# Sheet1.net
KiCad netlist of a schematic drawn in Altium Designer
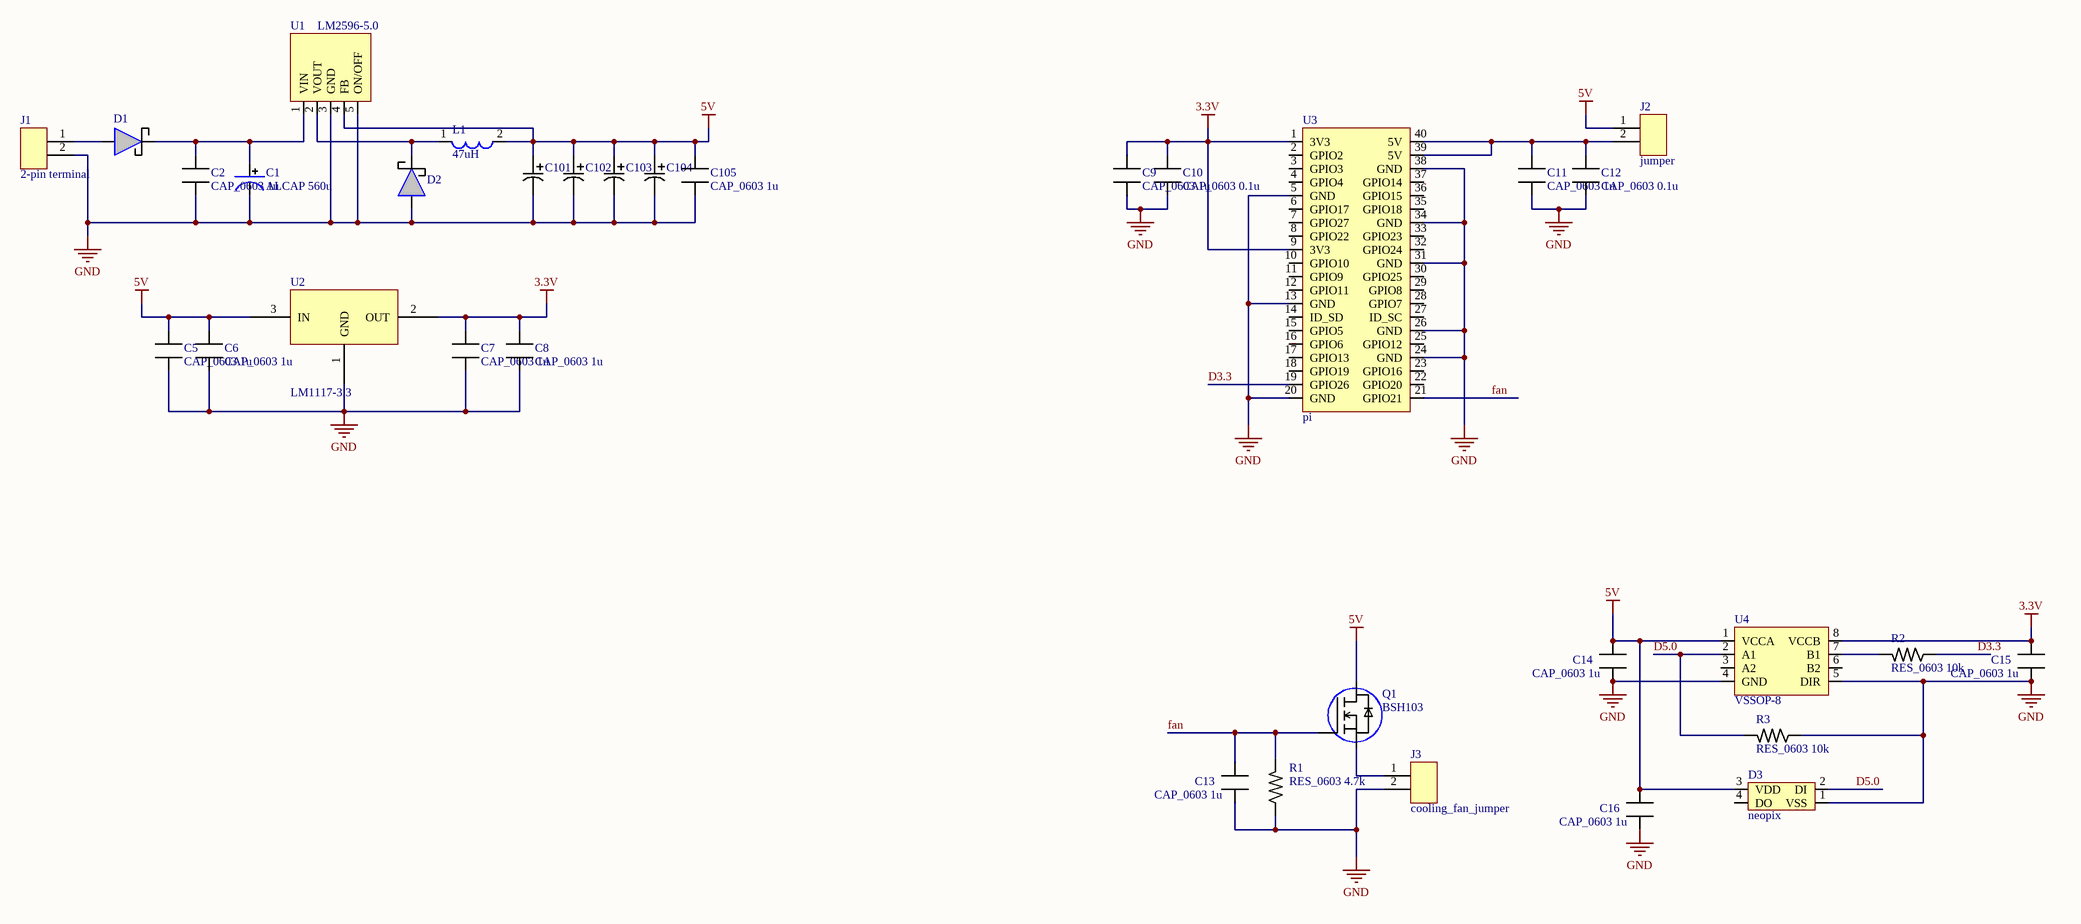
[diagram p0: Sheet1.SchDoc]

(export (version "E")
  (design (tool "Eeschema 10.0.6"))
  (components
    (comp (ref "C1")
      (value "ALCAP 560u")
      (footprint "alcap-560uF")
      (description "ALCAP")
      (libsource (lib "pi_powerhat") (part "ALCAP_47UF"))
    )
    (comp (ref "C2")
      (value "CAP_0603 1u")
      (footprint "CAP_0603")
      (description "CAP_0603")
      (libsource (lib "pi_powerhat") (part "CAP_0603"))
    )
    (comp (ref "C5")
      (value "CAP_0603 1u")
      (footprint "CAP_0603")
      (description "CAP_0603")
      (libsource (lib "pi_powerhat") (part "CAP_0603"))
    )
    (comp (ref "C6")
      (value "CAP_0603 1u")
      (footprint "CAP_0603")
      (description "CAP_0603")
      (libsource (lib "pi_powerhat") (part "CAP_0603"))
    )
    (comp (ref "C7")
      (value "CAP_0603 1u")
      (footprint "CAP_0603")
      (description "CAP_0603")
      (libsource (lib "pi_powerhat") (part "CAP_0603"))
    )
    (comp (ref "C8")
      (value "CAP_0603 1u")
      (footprint "CAP_0603")
      (description "CAP_0603")
      (libsource (lib "pi_powerhat") (part "CAP_0603"))
    )
    (comp (ref "C9")
      (value "CAP_0603 1u")
      (footprint "CAP_0603")
      (description "CAP_0603")
      (libsource (lib "pi_powerhat") (part "CAP_0603"))
    )
    (comp (ref "C10")
      (value "CAP_0603 0.1u")
      (footprint "CAP_0603")
      (description "CAP_0603")
      (libsource (lib "pi_powerhat") (part "CAP_0603"))
    )
    (comp (ref "C11")
      (value "CAP_0603 1u")
      (footprint "CAP_0603")
      (description "CAP_0603")
      (libsource (lib "pi_powerhat") (part "CAP_0603"))
    )
    (comp (ref "C12")
      (value "CAP_0603 0.1u")
      (footprint "CAP_0603")
      (description "CAP_0603")
      (libsource (lib "pi_powerhat") (part "CAP_0603"))
    )
    (comp (ref "C13")
      (value "CAP_0603 1u")
      (footprint "CAP_0603")
      (description "CAP_0603")
      (libsource (lib "pi_powerhat") (part "CAP_0603"))
    )
    (comp (ref "C14")
      (value "CAP_0603 1u")
      (footprint "CAP_0603")
      (description "CAP_0603")
      (libsource (lib "pi_powerhat") (part "CAP_0603"))
    )
    (comp (ref "C15")
      (value "CAP_0603 1u")
      (footprint "CAP_0603")
      (description "CAP_0603")
      (libsource (lib "pi_powerhat") (part "CAP_0603"))
    )
    (comp (ref "C16")
      (value "CAP_0603 1u")
      (footprint "CAP_0603")
      (description "CAP_0603")
      (libsource (lib "pi_powerhat") (part "CAP_0603"))
    )
    (comp (ref "C101")
      (value "Part Number: TAJC107K010RNJ")
      (footprint "TAJC")
      (description "No Description Available")
      (fields
        (field (name "MANUFACTURER_PART_NUMBER") "TAJC107K010RNJ")
        (field (name "COPYRIGHT") "Copyright (C) 2018 Accelerated Designs. All rights reserved")
      )
      (libsource (lib "pi_powerhat") (part "TAJC107K010RNJ"))
    )
    (comp (ref "C102")
      (value "Part Number: TAJC107K010RNJ")
      (footprint "TAJC")
      (description "No Description Available")
      (fields
        (field (name "MANUFACTURER_PART_NUMBER") "TAJC107K010RNJ")
        (field (name "COPYRIGHT") "Copyright (C) 2018 Accelerated Designs. All rights reserved")
      )
      (libsource (lib "pi_powerhat") (part "TAJC107K010RNJ"))
    )
    (comp (ref "C103")
      (value "Part Number: TAJC107K010RNJ")
      (footprint "TAJC")
      (description "No Description Available")
      (fields
        (field (name "MANUFACTURER_PART_NUMBER") "TAJC107K010RNJ")
        (field (name "COPYRIGHT") "Copyright (C) 2018 Accelerated Designs. All rights reserved")
      )
      (libsource (lib "pi_powerhat") (part "TAJC107K010RNJ"))
    )
    (comp (ref "C104")
      (value "Part Number: TAJC107K010RNJ")
      (footprint "TAJC")
      (description "No Description Available")
      (fields
        (field (name "MANUFACTURER_PART_NUMBER") "TAJC107K010RNJ")
        (field (name "COPYRIGHT") "Copyright (C) 2018 Accelerated Designs. All rights reserved")
      )
      (libsource (lib "pi_powerhat") (part "TAJC107K010RNJ"))
    )
    (comp (ref "C105")
      (value "CAP_0603 1u")
      (footprint "CAP_0603")
      (description "CAP_0603")
      (libsource (lib "pi_powerhat") (part "CAP_0603"))
    )
    (comp (ref "D1")
      (value "RBR3LAM60BTF_diode")
      (footprint "RBR3LAM60BTF_diode")
      (libsource (lib "pi_powerhat") (part "RBR3LAM60BTF_diode"))
    )
    (comp (ref "D2")
      (value "RBR3LAM60BTF_diode")
      (footprint "RBR3LAM60BTF_diode")
      (libsource (lib "pi_powerhat") (part "RBR3LAM60BTF_diode"))
    )
    (comp (ref "D3") (value "neopix") (footprint "neopix") (libsource (lib "pi_powerhat") (part "neopix")))
    (comp (ref "J1")
      (value "2-pin terminal")
      (footprint "2-pin terminal")
      (libsource (lib "pi_powerhat") (part "2-pin terminal"))
    )
    (comp (ref "J2")
      (value "jumper")
      (footprint "2pin_jumper")
      (libsource (lib "pi_powerhat") (part "2pin_jumper"))
    )
    (comp (ref "J3")
      (value "cooling_fan_jumper")
      (footprint "2pin_jumper")
      (libsource (lib "pi_powerhat") (part "2pin_jumper"))
    )
    (comp (ref "L1")
      (value "47uH")
      (footprint "732-11450-1-ND")
      (libsource (lib "pi_powerhat") (part "732-11450-1-ND"))
    )
    (comp (ref "Q1")
      (value "BSH103")
      (footprint "bsh103_MOS")
      (libsource (lib "pi_powerhat") (part "MOSFET_N_1"))
    )
    (comp (ref "R1")
      (value "RES_0603 4.7k")
      (footprint "RES_0603")
      (description "RES_0603 1/8 W")
      (libsource (lib "pi_powerhat") (part "RES_0603"))
    )
    (comp (ref "R2")
      (value "RES_0603 10k")
      (footprint "RES_0603")
      (description "RES_0603 1/8 W")
      (libsource (lib "pi_powerhat") (part "RES_0603"))
    )
    (comp (ref "R3")
      (value "RES_0603 10k")
      (footprint "RES_0603")
      (description "RES_0603 1/8 W")
      (libsource (lib "pi_powerhat") (part "RES_0603"))
    )
    (comp (ref "U1")
      (value "LM2596-5.0")
      (footprint "lm2956-5.0")
      (libsource (lib "pi_powerhat") (part "LM2596-5.0"))
    )
    (comp (ref "U2")
      (value "LM1117-3.3")
      (footprint "LM1117-3.3")
      (libsource (lib "pi_powerhat") (part "LM1117-3.3"))
    )
    (comp (ref "U3") (value "pi") (footprint "pi") (libsource (lib "pi_powerhat") (part "pi")))
    (comp (ref "U4")
      (value "VSSOP-8")
      (footprint "TSOP65P400X130-8M")
      (libsource (lib "pi_powerhat") (part "SN74LVC2T45"))
    )
  )
  (nets
    (net (code "1") (name "/D3.3") (class "Default")
      (node (ref "R2") (pin "1") (pinfunction "1_1") (pintype "passive"))
      (node (ref "U3") (pin "19") (pinfunction "GPIO26_19") (pintype "passive"))
    )
    (net (code "2") (name "/D5.0") (class "Default")
      (node (ref "D3") (pin "2") (pinfunction "DI_2") (pintype "passive"))
      (node (ref "R3") (pin "2") (pinfunction "2_2") (pintype "passive"))
      (node (ref "U4") (pin "2") (pinfunction "A1_2") (pintype "passive"))
    )
    (net (code "3") (name "/fan") (class "Default")
      (node (ref "C13") (pin "2") (pinfunction "2_2") (pintype "passive"))
      (node (ref "Q1") (pin "1") (pinfunction "G_1") (pintype "passive"))
      (node (ref "R1") (pin "2") (pinfunction "2_2") (pintype "passive"))
      (node (ref "U3") (pin "21") (pinfunction "GPIO21_21") (pintype "passive"))
    )
    (net (code "4") (name "3.3V") (class "Default")
      (node (ref "C10") (pin "2") (pinfunction "2_2") (pintype "passive"))
      (node (ref "C15") (pin "2") (pinfunction "2_2") (pintype "passive"))
      (node (ref "C7") (pin "2") (pinfunction "2_2") (pintype "passive"))
      (node (ref "C8") (pin "2") (pinfunction "2_2") (pintype "passive"))
      (node (ref "C9") (pin "2") (pinfunction "2_2") (pintype "passive"))
      (node (ref "U2") (pin "2") (pinfunction "OUT_2") (pintype "passive"))
      (node (ref "U3") (pin "1") (pinfunction "3V3_1") (pintype "passive"))
      (node (ref "U3") (pin "9") (pinfunction "3V3_9") (pintype "passive"))
      (node (ref "U4") (pin "8") (pinfunction "VCCB_8") (pintype "passive"))
    )
    (net (code "5") (name "5V") (class "Default")
      (node (ref "C101") (pin "1") (pinfunction "1_1") (pintype "passive"))
      (node (ref "C102") (pin "1") (pinfunction "1_1") (pintype "passive"))
      (node (ref "C103") (pin "1") (pinfunction "1_1") (pintype "passive"))
      (node (ref "C104") (pin "1") (pinfunction "1_1") (pintype "passive"))
      (node (ref "C105") (pin "2") (pinfunction "2_2") (pintype "passive"))
      (node (ref "C14") (pin "2") (pinfunction "2_2") (pintype "passive"))
      (node (ref "C16") (pin "2") (pinfunction "2_2") (pintype "passive"))
      (node (ref "C5") (pin "2") (pinfunction "2_2") (pintype "passive"))
      (node (ref "C6") (pin "2") (pinfunction "2_2") (pintype "passive"))
      (node (ref "D3") (pin "3") (pinfunction "VDD_3") (pintype "passive"))
      (node (ref "J2") (pin "1") (pinfunction "1_1") (pintype "passive"))
      (node (ref "L1") (pin "2") (pinfunction "2_2") (pintype "passive"))
      (node (ref "Q1") (pin "2") (pinfunction "D_2") (pintype "passive"))
      (node (ref "U1") (pin "4") (pinfunction "FB_4") (pintype "passive"))
      (node (ref "U2") (pin "3") (pinfunction "IN_3") (pintype "passive"))
      (node (ref "U4") (pin "1") (pinfunction "VCCA_1") (pintype "passive"))
    )
    (net (code "6") (name "GND") (class "Default")
      (node (ref "C1") (pin "2") (pinfunction "2_2") (pintype "passive"))
      (node (ref "C10") (pin "1") (pinfunction "1_1") (pintype "passive"))
      (node (ref "C101") (pin "2") (pinfunction "2_2") (pintype "passive"))
      (node (ref "C102") (pin "2") (pinfunction "2_2") (pintype "passive"))
      (node (ref "C103") (pin "2") (pinfunction "2_2") (pintype "passive"))
      (node (ref "C104") (pin "2") (pinfunction "2_2") (pintype "passive"))
      (node (ref "C105") (pin "1") (pinfunction "1_1") (pintype "passive"))
      (node (ref "C11") (pin "1") (pinfunction "1_1") (pintype "passive"))
      (node (ref "C12") (pin "1") (pinfunction "1_1") (pintype "passive"))
      (node (ref "C13") (pin "1") (pinfunction "1_1") (pintype "passive"))
      (node (ref "C14") (pin "1") (pinfunction "1_1") (pintype "passive"))
      (node (ref "C15") (pin "1") (pinfunction "1_1") (pintype "passive"))
      (node (ref "C16") (pin "1") (pinfunction "1_1") (pintype "passive"))
      (node (ref "C2") (pin "1") (pinfunction "1_1") (pintype "passive"))
      (node (ref "C5") (pin "1") (pinfunction "1_1") (pintype "passive"))
      (node (ref "C6") (pin "1") (pinfunction "1_1") (pintype "passive"))
      (node (ref "C7") (pin "1") (pinfunction "1_1") (pintype "passive"))
      (node (ref "C8") (pin "1") (pinfunction "1_1") (pintype "passive"))
      (node (ref "C9") (pin "1") (pinfunction "1_1") (pintype "passive"))
      (node (ref "D2") (pin "2") (pinfunction "2_2") (pintype "passive"))
      (node (ref "D3") (pin "1") (pinfunction "VSS_1") (pintype "passive"))
      (node (ref "J1") (pin "2") (pinfunction "2_2") (pintype "passive"))
      (node (ref "J3") (pin "2") (pinfunction "2_2") (pintype "passive"))
      (node (ref "R1") (pin "1") (pinfunction "1_1") (pintype "passive"))
      (node (ref "R3") (pin "1") (pinfunction "1_1") (pintype "passive"))
      (node (ref "U1") (pin "3") (pinfunction "GND_3") (pintype "passive"))
      (node (ref "U1") (pin "5") (pinfunction "ON/OFF_5") (pintype "passive"))
      (node (ref "U2") (pin "1") (pinfunction "GND_1") (pintype "passive"))
      (node (ref "U3") (pin "13") (pinfunction "GND_13") (pintype "passive"))
      (node (ref "U3") (pin "20") (pinfunction "GND_20") (pintype "passive"))
      (node (ref "U3") (pin "24") (pinfunction "GND_24") (pintype "passive"))
      (node (ref "U3") (pin "26") (pinfunction "GND_26") (pintype "passive"))
      (node (ref "U3") (pin "31") (pinfunction "GND_31") (pintype "passive"))
      (node (ref "U3") (pin "34") (pinfunction "GND_34") (pintype "passive"))
      (node (ref "U3") (pin "38") (pinfunction "GND_38") (pintype "passive"))
      (node (ref "U3") (pin "5") (pinfunction "GND_5") (pintype "passive"))
      (node (ref "U4") (pin "4") (pinfunction "GND_4") (pintype "passive"))
      (node (ref "U4") (pin "5") (pinfunction "DIR_5") (pintype "passive"))
    )
    (net (code "7") (name "Net-(C11-Pad2)") (class "Default")
      (node (ref "C11") (pin "2") (pinfunction "2_2") (pintype "passive"))
      (node (ref "C12") (pin "2") (pinfunction "2_2") (pintype "passive"))
      (node (ref "J2") (pin "2") (pinfunction "2_2") (pintype "passive"))
      (node (ref "U3") (pin "39") (pinfunction "5V_39") (pintype "passive"))
      (node (ref "U3") (pin "40") (pinfunction "5V_40") (pintype "passive"))
    )
    (net (code "8") (name "Net-(D1-Pad2)") (class "Default")
      (node (ref "D1") (pin "2") (pinfunction "2_2") (pintype "passive"))
      (node (ref "J1") (pin "1") (pinfunction "1_1") (pintype "passive"))
    )
    (net (code "9") (name "Net-(Q1-S)") (class "Default")
      (node (ref "J3") (pin "1") (pinfunction "1_1") (pintype "passive"))
      (node (ref "Q1") (pin "3") (pinfunction "S_3") (pintype "passive"))
    )
    (net (code "10") (name "Net-(U1-VIN)") (class "Default")
      (node (ref "C1") (pin "1") (pinfunction "1_1") (pintype "passive"))
      (node (ref "C2") (pin "2") (pinfunction "2_2") (pintype "passive"))
      (node (ref "D1") (pin "1") (pinfunction "1_1") (pintype "passive"))
      (node (ref "U1") (pin "1") (pinfunction "VIN_1") (pintype "passive"))
    )
    (net (code "11") (name "Net-(U1-VOUT)") (class "Default")
      (node (ref "D2") (pin "1") (pinfunction "1_1") (pintype "passive"))
      (node (ref "L1") (pin "1") (pinfunction "1_1") (pintype "passive"))
      (node (ref "U1") (pin "2") (pinfunction "VOUT_2") (pintype "passive"))
    )
    (net (code "12") (name "Net-(U4-B1)") (class "Default")
      (node (ref "R2") (pin "2") (pinfunction "2_2") (pintype "passive"))
      (node (ref "U4") (pin "7") (pinfunction "B1_7") (pintype "passive"))
    )
    (net (code "13") (name "unconnected-(D3-DO-Pad4)") (class "Default")
      (node (ref "D3") (pin "4") (pinfunction "DO_4") (pintype "passive"))
    )
    (net (code "14") (name "unconnected-(U3-GPIO2-Pad2)") (class "Default")
      (node (ref "U3") (pin "2") (pinfunction "GPIO2_2") (pintype "passive"))
    )
    (net (code "15") (name "unconnected-(U3-GPIO3-Pad3)") (class "Default")
      (node (ref "U3") (pin "3") (pinfunction "GPIO3_3") (pintype "passive"))
    )
    (net (code "16") (name "unconnected-(U3-GPIO4-Pad4)") (class "Default")
      (node (ref "U3") (pin "4") (pinfunction "GPIO4_4") (pintype "passive"))
    )
    (net (code "17") (name "unconnected-(U3-GPIO5-Pad15)") (class "Default")
      (node (ref "U3") (pin "15") (pinfunction "GPIO5_15") (pintype "passive"))
    )
    (net (code "18") (name "unconnected-(U3-GPIO6-Pad16)") (class "Default")
      (node (ref "U3") (pin "16") (pinfunction "GPIO6_16") (pintype "passive"))
    )
    (net (code "19") (name "unconnected-(U3-GPIO7-Pad28)") (class "Default")
      (node (ref "U3") (pin "28") (pinfunction "GPIO7_28") (pintype "passive"))
    )
    (net (code "20") (name "unconnected-(U3-GPIO8-Pad29)") (class "Default")
      (node (ref "U3") (pin "29") (pinfunction "GPIO8_29") (pintype "passive"))
    )
    (net (code "21") (name "unconnected-(U3-GPIO9-Pad11)") (class "Default")
      (node (ref "U3") (pin "11") (pinfunction "GPIO9_11") (pintype "passive"))
    )
    (net (code "22") (name "unconnected-(U3-GPIO10-Pad10)") (class "Default")
      (node (ref "U3") (pin "10") (pinfunction "GPIO10_10") (pintype "passive"))
    )
    (net (code "23") (name "unconnected-(U3-GPIO11-Pad12)") (class "Default")
      (node (ref "U3") (pin "12") (pinfunction "GPIO11_12") (pintype "passive"))
    )
    (net (code "24") (name "unconnected-(U3-GPIO12-Pad25)") (class "Default")
      (node (ref "U3") (pin "25") (pinfunction "GPIO12_25") (pintype "passive"))
    )
    (net (code "25") (name "unconnected-(U3-GPIO13-Pad17)") (class "Default")
      (node (ref "U3") (pin "17") (pinfunction "GPIO13_17") (pintype "passive"))
    )
    (net (code "26") (name "unconnected-(U3-GPIO14-Pad37)") (class "Default")
      (node (ref "U3") (pin "37") (pinfunction "GPIO14_37") (pintype "passive"))
    )
    (net (code "27") (name "unconnected-(U3-GPIO15-Pad36)") (class "Default")
      (node (ref "U3") (pin "36") (pinfunction "GPIO15_36") (pintype "passive"))
    )
    (net (code "28") (name "unconnected-(U3-GPIO16-Pad23)") (class "Default")
      (node (ref "U3") (pin "23") (pinfunction "GPIO16_23") (pintype "passive"))
    )
    (net (code "29") (name "unconnected-(U3-GPIO17-Pad6)") (class "Default")
      (node (ref "U3") (pin "6") (pinfunction "GPIO17_6") (pintype "passive"))
    )
    (net (code "30") (name "unconnected-(U3-GPIO18-Pad35)") (class "Default")
      (node (ref "U3") (pin "35") (pinfunction "GPIO18_35") (pintype "passive"))
    )
    (net (code "31") (name "unconnected-(U3-GPIO19-Pad18)") (class "Default")
      (node (ref "U3") (pin "18") (pinfunction "GPIO19_18") (pintype "passive"))
    )
    (net (code "32") (name "unconnected-(U3-GPIO20-Pad22)") (class "Default")
      (node (ref "U3") (pin "22") (pinfunction "GPIO20_22") (pintype "passive"))
    )
    (net (code "33") (name "unconnected-(U3-GPIO22-Pad8)") (class "Default")
      (node (ref "U3") (pin "8") (pinfunction "GPIO22_8") (pintype "passive"))
    )
    (net (code "34") (name "unconnected-(U3-GPIO23-Pad33)") (class "Default")
      (node (ref "U3") (pin "33") (pinfunction "GPIO23_33") (pintype "passive"))
    )
    (net (code "35") (name "unconnected-(U3-GPIO24-Pad32)") (class "Default")
      (node (ref "U3") (pin "32") (pinfunction "GPIO24_32") (pintype "passive"))
    )
    (net (code "36") (name "unconnected-(U3-GPIO25-Pad30)") (class "Default")
      (node (ref "U3") (pin "30") (pinfunction "GPIO25_30") (pintype "passive"))
    )
    (net (code "37") (name "unconnected-(U3-GPIO27-Pad7)") (class "Default")
      (node (ref "U3") (pin "7") (pinfunction "GPIO27_7") (pintype "passive"))
    )
    (net (code "38") (name "unconnected-(U3-ID_SC-Pad27)") (class "Default")
      (node (ref "U3") (pin "27") (pinfunction "ID_SC_27") (pintype "passive"))
    )
    (net (code "39") (name "unconnected-(U3-ID_SD-Pad14)") (class "Default")
      (node (ref "U3") (pin "14") (pinfunction "ID_SD_14") (pintype "passive"))
    )
    (net (code "40") (name "unconnected-(U4-A2-Pad3)") (class "Default")
      (node (ref "U4") (pin "3") (pinfunction "A2_3") (pintype "passive"))
    )
    (net (code "41") (name "unconnected-(U4-B2-Pad6)") (class "Default")
      (node (ref "U4") (pin "6") (pinfunction "B2_6") (pintype "passive"))
    )
  )
)
